# IO_board2.net
KiCad netlist of a schematic drawn in Altium Designer
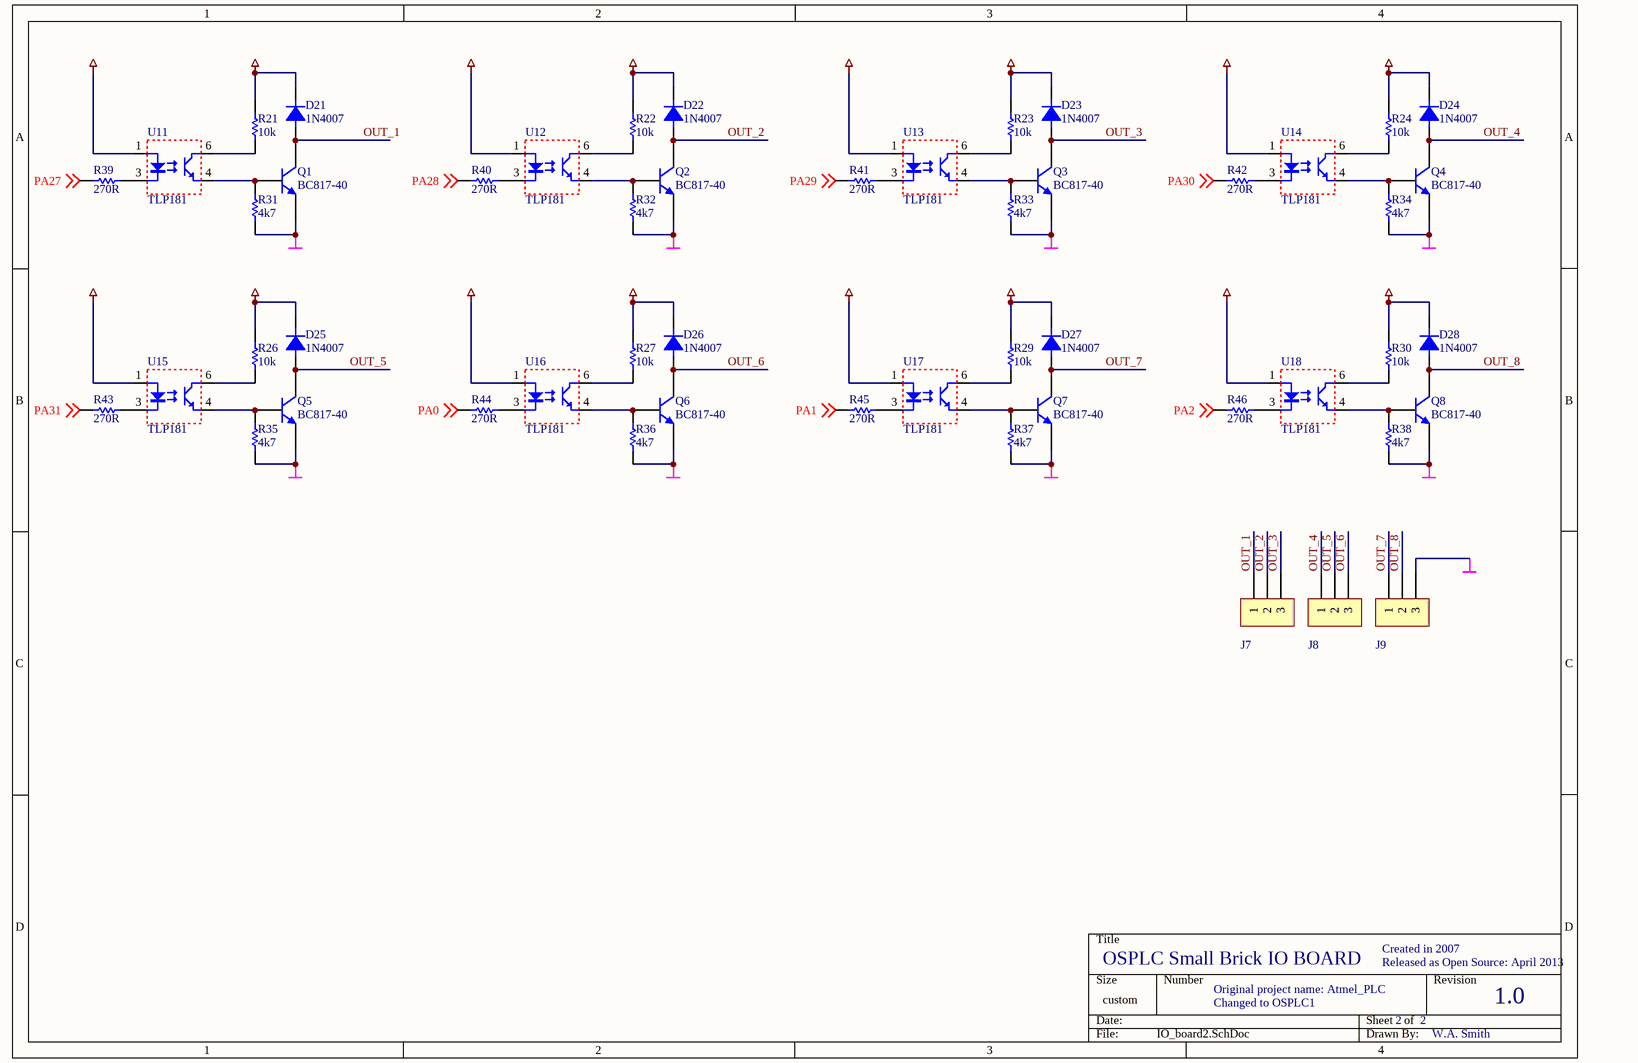
[diagram p0: IO_board2.SchDoc]

(export (version "E")
  (design (tool "Eeschema 10.0.6"))
  (components
    (comp (ref "D21")
      (value "1N4007 Radialy Mounted")
      (footprint "DIODE_RAD_3MM")
      (description "1N4007 Rectifier Diode Radialy Mounted")
      (fields (field (name "ALTIUM_VALUE") "1N4007"))
      (libsource (lib "ARM_projects") (part "1N4007"))
    )
    (comp (ref "D22")
      (value "1N4007 Radialy Mounted")
      (footprint "DIODE_RAD_3MM")
      (description "1N4007 Rectifier Diode Radialy Mounted")
      (fields (field (name "ALTIUM_VALUE") "1N4007"))
      (libsource (lib "ARM_projects") (part "1N4007"))
    )
    (comp (ref "D23")
      (value "1N4007 Radialy Mounted")
      (footprint "DIODE_RAD_3MM")
      (description "1N4007 Rectifier Diode Radialy Mounted")
      (fields (field (name "ALTIUM_VALUE") "1N4007"))
      (libsource (lib "ARM_projects") (part "1N4007"))
    )
    (comp (ref "D24")
      (value "1N4007 Radialy Mounted")
      (footprint "DIODE_RAD_3MM")
      (description "1N4007 Rectifier Diode Radialy Mounted")
      (fields (field (name "ALTIUM_VALUE") "1N4007"))
      (libsource (lib "ARM_projects") (part "1N4007"))
    )
    (comp (ref "D25")
      (value "1N4007 Radialy Mounted")
      (footprint "DIODE_RAD_3MM")
      (description "1N4007 Rectifier Diode Radialy Mounted")
      (fields (field (name "ALTIUM_VALUE") "1N4007"))
      (libsource (lib "ARM_projects") (part "1N4007"))
    )
    (comp (ref "D26")
      (value "1N4007 Radialy Mounted")
      (footprint "DIODE_RAD_3MM")
      (description "1N4007 Rectifier Diode Radialy Mounted")
      (fields (field (name "ALTIUM_VALUE") "1N4007"))
      (libsource (lib "ARM_projects") (part "1N4007"))
    )
    (comp (ref "D27")
      (value "1N4007 Radialy Mounted")
      (footprint "DIODE_RAD_3MM")
      (description "1N4007 Rectifier Diode Radialy Mounted")
      (fields (field (name "ALTIUM_VALUE") "1N4007"))
      (libsource (lib "ARM_projects") (part "1N4007"))
    )
    (comp (ref "D28")
      (value "1N4007 Radialy Mounted")
      (footprint "DIODE_RAD_3MM")
      (description "1N4007 Rectifier Diode Radialy Mounted")
      (fields (field (name "ALTIUM_VALUE") "1N4007"))
      (libsource (lib "ARM_projects") (part "1N4007"))
    )
    (comp (ref "J7")
      (value "PCB TERMINAL")
      (footprint "TERMINAL_3WAY_5MM")
      (description "5mm spaced PCB terminal, 3 pole")
      (libsource (lib "ARM_projects") (part "TERMINAL_3WAY_5MM"))
    )
    (comp (ref "J8")
      (value "PCB TERMINAL")
      (footprint "TERMINAL_3WAY_5MM")
      (description "5mm spaced PCB terminal, 3 pole")
      (libsource (lib "ARM_projects") (part "TERMINAL_3WAY_5MM"))
    )
    (comp (ref "J9")
      (value "PCB TERMINAL")
      (footprint "TERMINAL_3WAY_5MM")
      (description "5mm spaced PCB terminal, 3 pole")
      (libsource (lib "ARM_projects") (part "TERMINAL_3WAY_5MM"))
    )
    (comp (ref "Q1")
      (value "BC817-40")
      (footprint "SO-G3/Y1")
      (description "NPN General Purpose Amplifier")
      (fields
        (field (name "MANUFACTURER") "Fairchild Semiconductor")
        (field (name "PUBLISHER") "Altium Limited")
      )
      (libsource (lib "FSC Discrete BJT") (part "BC817-40"))
    )
    (comp (ref "Q2")
      (value "BC817-40")
      (footprint "SO-G3/Y1")
      (description "NPN General Purpose Amplifier")
      (fields
        (field (name "MANUFACTURER") "Fairchild Semiconductor")
        (field (name "PUBLISHER") "Altium Limited")
      )
      (libsource (lib "FSC Discrete BJT") (part "BC817-40"))
    )
    (comp (ref "Q3")
      (value "BC817-40")
      (footprint "SO-G3/Y1")
      (description "NPN General Purpose Amplifier")
      (fields
        (field (name "MANUFACTURER") "Fairchild Semiconductor")
        (field (name "PUBLISHER") "Altium Limited")
      )
      (libsource (lib "FSC Discrete BJT") (part "BC817-40"))
    )
    (comp (ref "Q4")
      (value "BC817-40")
      (footprint "SO-G3/Y1")
      (description "NPN General Purpose Amplifier")
      (fields
        (field (name "MANUFACTURER") "Fairchild Semiconductor")
        (field (name "PUBLISHER") "Altium Limited")
      )
      (libsource (lib "FSC Discrete BJT") (part "BC817-40"))
    )
    (comp (ref "Q5")
      (value "BC817-40")
      (footprint "SO-G3/Y1")
      (description "NPN General Purpose Amplifier")
      (fields
        (field (name "MANUFACTURER") "Fairchild Semiconductor")
        (field (name "PUBLISHER") "Altium Limited")
      )
      (libsource (lib "FSC Discrete BJT") (part "BC817-40"))
    )
    (comp (ref "Q6")
      (value "BC817-40")
      (footprint "SO-G3/Y1")
      (description "NPN General Purpose Amplifier")
      (fields
        (field (name "MANUFACTURER") "Fairchild Semiconductor")
        (field (name "PUBLISHER") "Altium Limited")
      )
      (libsource (lib "FSC Discrete BJT") (part "BC817-40"))
    )
    (comp (ref "Q7")
      (value "BC817-40")
      (footprint "SO-G3/Y1")
      (description "NPN General Purpose Amplifier")
      (fields
        (field (name "MANUFACTURER") "Fairchild Semiconductor")
        (field (name "PUBLISHER") "Altium Limited")
      )
      (libsource (lib "FSC Discrete BJT") (part "BC817-40"))
    )
    (comp (ref "Q8")
      (value "BC817-40")
      (footprint "SO-G3/Y1")
      (description "NPN General Purpose Amplifier")
      (fields
        (field (name "MANUFACTURER") "Fairchild Semiconductor")
        (field (name "PUBLISHER") "Altium Limited")
      )
      (libsource (lib "FSC Discrete BJT") (part "BC817-40"))
    )
    (comp (ref "R21")
      (value "0805")
      (footprint "0805")
      (description "0805 footprint resistor")
      (fields (field (name "ALTIUM_VALUE") "10k"))
      (libsource (lib "Integrated Comp_lib") (part "RES_0805"))
    )
    (comp (ref "R22")
      (value "0805")
      (footprint "0805")
      (description "0805 footprint resistor")
      (fields (field (name "ALTIUM_VALUE") "10k"))
      (libsource (lib "Integrated Comp_lib") (part "RES_0805"))
    )
    (comp (ref "R23")
      (value "0805")
      (footprint "0805")
      (description "0805 footprint resistor")
      (fields (field (name "ALTIUM_VALUE") "10k"))
      (libsource (lib "Integrated Comp_lib") (part "RES_0805"))
    )
    (comp (ref "R24")
      (value "0805")
      (footprint "0805")
      (description "0805 footprint resistor")
      (fields (field (name "ALTIUM_VALUE") "10k"))
      (libsource (lib "Integrated Comp_lib") (part "RES_0805"))
    )
    (comp (ref "R26")
      (value "0805")
      (footprint "0805")
      (description "0805 footprint resistor")
      (fields (field (name "ALTIUM_VALUE") "10k"))
      (libsource (lib "Integrated Comp_lib") (part "RES_0805"))
    )
    (comp (ref "R27")
      (value "0805")
      (footprint "0805")
      (description "0805 footprint resistor")
      (fields (field (name "ALTIUM_VALUE") "10k"))
      (libsource (lib "Integrated Comp_lib") (part "RES_0805"))
    )
    (comp (ref "R29")
      (value "0805")
      (footprint "0805")
      (description "0805 footprint resistor")
      (fields (field (name "ALTIUM_VALUE") "10k"))
      (libsource (lib "Integrated Comp_lib") (part "RES_0805"))
    )
    (comp (ref "R30")
      (value "0805")
      (footprint "0805")
      (description "0805 footprint resistor")
      (fields (field (name "ALTIUM_VALUE") "10k"))
      (libsource (lib "Integrated Comp_lib") (part "RES_0805"))
    )
    (comp (ref "R31")
      (value "0805")
      (footprint "0805")
      (description "0805 footprint resistor")
      (fields (field (name "ALTIUM_VALUE") "4k7"))
      (libsource (lib "Integrated Comp_lib") (part "RES_0805"))
    )
    (comp (ref "R32")
      (value "0805")
      (footprint "0805")
      (description "0805 footprint resistor")
      (fields (field (name "ALTIUM_VALUE") "4k7"))
      (libsource (lib "Integrated Comp_lib") (part "RES_0805"))
    )
    (comp (ref "R33")
      (value "0805")
      (footprint "0805")
      (description "0805 footprint resistor")
      (fields (field (name "ALTIUM_VALUE") "4k7"))
      (libsource (lib "Integrated Comp_lib") (part "RES_0805"))
    )
    (comp (ref "R34")
      (value "0805")
      (footprint "0805")
      (description "0805 footprint resistor")
      (fields (field (name "ALTIUM_VALUE") "4k7"))
      (libsource (lib "Integrated Comp_lib") (part "RES_0805"))
    )
    (comp (ref "R35")
      (value "0805")
      (footprint "0805")
      (description "0805 footprint resistor")
      (fields (field (name "ALTIUM_VALUE") "4k7"))
      (libsource (lib "Integrated Comp_lib") (part "RES_0805"))
    )
    (comp (ref "R36")
      (value "0805")
      (footprint "0805")
      (description "0805 footprint resistor")
      (fields (field (name "ALTIUM_VALUE") "4k7"))
      (libsource (lib "Integrated Comp_lib") (part "RES_0805"))
    )
    (comp (ref "R37")
      (value "0805")
      (footprint "0805")
      (description "0805 footprint resistor")
      (fields (field (name "ALTIUM_VALUE") "4k7"))
      (libsource (lib "Integrated Comp_lib") (part "RES_0805"))
    )
    (comp (ref "R38")
      (value "0805")
      (footprint "0805")
      (description "0805 footprint resistor")
      (fields (field (name "ALTIUM_VALUE") "4k7"))
      (libsource (lib "Integrated Comp_lib") (part "RES_0805"))
    )
    (comp (ref "R39")
      (value "0805")
      (footprint "0805")
      (description "0805 footprint resistor")
      (fields (field (name "ALTIUM_VALUE") "270R"))
      (libsource (lib "Integrated Comp_lib") (part "RES_0805"))
    )
    (comp (ref "R40")
      (value "0805")
      (footprint "0805")
      (description "0805 footprint resistor")
      (fields (field (name "ALTIUM_VALUE") "270R"))
      (libsource (lib "Integrated Comp_lib") (part "RES_0805"))
    )
    (comp (ref "R41")
      (value "0805")
      (footprint "0805")
      (description "0805 footprint resistor")
      (fields (field (name "ALTIUM_VALUE") "270R"))
      (libsource (lib "Integrated Comp_lib") (part "RES_0805"))
    )
    (comp (ref "R42")
      (value "0805")
      (footprint "0805")
      (description "0805 footprint resistor")
      (fields (field (name "ALTIUM_VALUE") "270R"))
      (libsource (lib "Integrated Comp_lib") (part "RES_0805"))
    )
    (comp (ref "R43")
      (value "0805")
      (footprint "0805")
      (description "0805 footprint resistor")
      (fields (field (name "ALTIUM_VALUE") "270R"))
      (libsource (lib "Integrated Comp_lib") (part "RES_0805"))
    )
    (comp (ref "R44")
      (value "0805")
      (footprint "0805")
      (description "0805 footprint resistor")
      (fields (field (name "ALTIUM_VALUE") "270R"))
      (libsource (lib "Integrated Comp_lib") (part "RES_0805"))
    )
    (comp (ref "R45")
      (value "0805")
      (footprint "0805")
      (description "0805 footprint resistor")
      (fields (field (name "ALTIUM_VALUE") "270R"))
      (libsource (lib "Integrated Comp_lib") (part "RES_0805"))
    )
    (comp (ref "R46")
      (value "0805")
      (footprint "0805")
      (description "0805 footprint resistor")
      (fields (field (name "ALTIUM_VALUE") "270R"))
      (libsource (lib "Integrated Comp_lib") (part "RES_0805"))
    )
    (comp (ref "U11")
      (value "TLP181")
      (footprint "SOP4_2.54")
      (description "Toshiba Photocoupler")
      (libsource (lib "Integrated Comp_lib") (part "TLP181"))
    )
    (comp (ref "U12")
      (value "TLP181")
      (footprint "SOP4_2.54")
      (description "Toshiba Photocoupler")
      (libsource (lib "Integrated Comp_lib") (part "TLP181"))
    )
    (comp (ref "U13")
      (value "TLP181")
      (footprint "SOP4_2.54")
      (description "Toshiba Photocoupler")
      (libsource (lib "Integrated Comp_lib") (part "TLP181"))
    )
    (comp (ref "U14")
      (value "TLP181")
      (footprint "SOP4_2.54")
      (description "Toshiba Photocoupler")
      (libsource (lib "Integrated Comp_lib") (part "TLP181"))
    )
    (comp (ref "U15")
      (value "TLP181")
      (footprint "SOP4_2.54")
      (description "Toshiba Photocoupler")
      (libsource (lib "Integrated Comp_lib") (part "TLP181"))
    )
    (comp (ref "U16")
      (value "TLP181")
      (footprint "SOP4_2.54")
      (description "Toshiba Photocoupler")
      (libsource (lib "Integrated Comp_lib") (part "TLP181"))
    )
    (comp (ref "U17")
      (value "TLP181")
      (footprint "SOP4_2.54")
      (description "Toshiba Photocoupler")
      (libsource (lib "Integrated Comp_lib") (part "TLP181"))
    )
    (comp (ref "U18")
      (value "TLP181")
      (footprint "SOP4_2.54")
      (description "Toshiba Photocoupler")
      (libsource (lib "Integrated Comp_lib") (part "TLP181"))
    )
  )
  (nets
    (net (code "1") (name "/OUT_1") (class "Default")
      (node (ref "D21") (pin "2") (pinfunction "A_2") (pintype "passive"))
      (node (ref "J7") (pin "1") (pinfunction "1_1") (pintype "passive"))
      (node (ref "Q1") (pin "3") (pinfunction "C_3") (pintype "passive"))
    )
    (net (code "2") (name "/OUT_2") (class "Default")
      (node (ref "D22") (pin "2") (pinfunction "A_2") (pintype "passive"))
      (node (ref "J7") (pin "2") (pinfunction "2_2") (pintype "passive"))
      (node (ref "Q2") (pin "3") (pinfunction "C_3") (pintype "passive"))
    )
    (net (code "3") (name "/OUT_3") (class "Default")
      (node (ref "D23") (pin "2") (pinfunction "A_2") (pintype "passive"))
      (node (ref "J7") (pin "3") (pinfunction "3_3") (pintype "passive"))
      (node (ref "Q3") (pin "3") (pinfunction "C_3") (pintype "passive"))
    )
    (net (code "4") (name "/OUT_4") (class "Default")
      (node (ref "D24") (pin "2") (pinfunction "A_2") (pintype "passive"))
      (node (ref "J8") (pin "1") (pinfunction "1_1") (pintype "passive"))
      (node (ref "Q4") (pin "3") (pinfunction "C_3") (pintype "passive"))
    )
    (net (code "5") (name "/OUT_5") (class "Default")
      (node (ref "D25") (pin "2") (pinfunction "A_2") (pintype "passive"))
      (node (ref "J8") (pin "2") (pinfunction "2_2") (pintype "passive"))
      (node (ref "Q5") (pin "3") (pinfunction "C_3") (pintype "passive"))
    )
    (net (code "6") (name "/OUT_6") (class "Default")
      (node (ref "D26") (pin "2") (pinfunction "A_2") (pintype "passive"))
      (node (ref "J8") (pin "3") (pinfunction "3_3") (pintype "passive"))
      (node (ref "Q6") (pin "3") (pinfunction "C_3") (pintype "passive"))
    )
    (net (code "7") (name "/OUT_7") (class "Default")
      (node (ref "D27") (pin "2") (pinfunction "A_2") (pintype "passive"))
      (node (ref "J9") (pin "1") (pinfunction "1_1") (pintype "passive"))
      (node (ref "Q7") (pin "3") (pinfunction "C_3") (pintype "passive"))
    )
    (net (code "8") (name "/OUT_8") (class "Default")
      (node (ref "D28") (pin "2") (pinfunction "A_2") (pintype "passive"))
      (node (ref "J9") (pin "2") (pinfunction "2_2") (pintype "passive"))
      (node (ref "Q8") (pin "3") (pinfunction "C_3") (pintype "passive"))
    )
    (net (code "9") (name "Net-(Q1-B)") (class "Default")
      (node (ref "Q1") (pin "1") (pinfunction "B_1") (pintype "passive"))
      (node (ref "R31") (pin "2") (pinfunction "2_2") (pintype "passive"))
      (node (ref "U11") (pin "4") (pinfunction "4_4") (pintype "passive"))
    )
    (net (code "10") (name "Net-(Q2-B)") (class "Default")
      (node (ref "Q2") (pin "1") (pinfunction "B_1") (pintype "passive"))
      (node (ref "R32") (pin "2") (pinfunction "2_2") (pintype "passive"))
      (node (ref "U12") (pin "4") (pinfunction "4_4") (pintype "passive"))
    )
    (net (code "11") (name "Net-(Q3-B)") (class "Default")
      (node (ref "Q3") (pin "1") (pinfunction "B_1") (pintype "passive"))
      (node (ref "R33") (pin "2") (pinfunction "2_2") (pintype "passive"))
      (node (ref "U13") (pin "4") (pinfunction "4_4") (pintype "passive"))
    )
    (net (code "12") (name "Net-(Q4-B)") (class "Default")
      (node (ref "Q4") (pin "1") (pinfunction "B_1") (pintype "passive"))
      (node (ref "R34") (pin "2") (pinfunction "2_2") (pintype "passive"))
      (node (ref "U14") (pin "4") (pinfunction "4_4") (pintype "passive"))
    )
    (net (code "13") (name "Net-(Q5-B)") (class "Default")
      (node (ref "Q5") (pin "1") (pinfunction "B_1") (pintype "passive"))
      (node (ref "R35") (pin "2") (pinfunction "2_2") (pintype "passive"))
      (node (ref "U15") (pin "4") (pinfunction "4_4") (pintype "passive"))
    )
    (net (code "14") (name "Net-(Q6-B)") (class "Default")
      (node (ref "Q6") (pin "1") (pinfunction "B_1") (pintype "passive"))
      (node (ref "R36") (pin "2") (pinfunction "2_2") (pintype "passive"))
      (node (ref "U16") (pin "4") (pinfunction "4_4") (pintype "passive"))
    )
    (net (code "15") (name "Net-(Q7-B)") (class "Default")
      (node (ref "Q7") (pin "1") (pinfunction "B_1") (pintype "passive"))
      (node (ref "R37") (pin "2") (pinfunction "2_2") (pintype "passive"))
      (node (ref "U17") (pin "4") (pinfunction "4_4") (pintype "passive"))
    )
    (net (code "16") (name "Net-(Q8-B)") (class "Default")
      (node (ref "Q8") (pin "1") (pinfunction "B_1") (pintype "passive"))
      (node (ref "R38") (pin "2") (pinfunction "2_2") (pintype "passive"))
      (node (ref "U18") (pin "4") (pinfunction "4_4") (pintype "passive"))
    )
    (net (code "17") (name "Net-(R21-Pad1)") (class "Default")
      (node (ref "R21") (pin "1") (pinfunction "1_1") (pintype "passive"))
      (node (ref "U11") (pin "6") (pinfunction "6_6") (pintype "passive"))
    )
    (net (code "18") (name "Net-(R22-Pad1)") (class "Default")
      (node (ref "R22") (pin "1") (pinfunction "1_1") (pintype "passive"))
      (node (ref "U12") (pin "6") (pinfunction "6_6") (pintype "passive"))
    )
    (net (code "19") (name "Net-(R23-Pad1)") (class "Default")
      (node (ref "R23") (pin "1") (pinfunction "1_1") (pintype "passive"))
      (node (ref "U13") (pin "6") (pinfunction "6_6") (pintype "passive"))
    )
    (net (code "20") (name "Net-(R24-Pad1)") (class "Default")
      (node (ref "R24") (pin "1") (pinfunction "1_1") (pintype "passive"))
      (node (ref "U14") (pin "6") (pinfunction "6_6") (pintype "passive"))
    )
    (net (code "21") (name "Net-(R26-Pad1)") (class "Default")
      (node (ref "R26") (pin "1") (pinfunction "1_1") (pintype "passive"))
      (node (ref "U15") (pin "6") (pinfunction "6_6") (pintype "passive"))
    )
    (net (code "22") (name "Net-(R27-Pad1)") (class "Default")
      (node (ref "R27") (pin "1") (pinfunction "1_1") (pintype "passive"))
      (node (ref "U16") (pin "6") (pinfunction "6_6") (pintype "passive"))
    )
    (net (code "23") (name "Net-(R29-Pad1)") (class "Default")
      (node (ref "R29") (pin "1") (pinfunction "1_1") (pintype "passive"))
      (node (ref "U17") (pin "6") (pinfunction "6_6") (pintype "passive"))
    )
    (net (code "24") (name "Net-(R30-Pad1)") (class "Default")
      (node (ref "R30") (pin "1") (pinfunction "1_1") (pintype "passive"))
      (node (ref "U18") (pin "6") (pinfunction "6_6") (pintype "passive"))
    )
    (net (code "25") (name "Net-(R39-Pad2)") (class "Default")
      (node (ref "R39") (pin "2") (pinfunction "2_2") (pintype "passive"))
      (node (ref "U11") (pin "3") (pinfunction "3_3") (pintype "passive"))
    )
    (net (code "26") (name "Net-(R40-Pad2)") (class "Default")
      (node (ref "R40") (pin "2") (pinfunction "2_2") (pintype "passive"))
      (node (ref "U12") (pin "3") (pinfunction "3_3") (pintype "passive"))
    )
    (net (code "27") (name "Net-(R41-Pad2)") (class "Default")
      (node (ref "R41") (pin "2") (pinfunction "2_2") (pintype "passive"))
      (node (ref "U13") (pin "3") (pinfunction "3_3") (pintype "passive"))
    )
    (net (code "28") (name "Net-(R42-Pad2)") (class "Default")
      (node (ref "R42") (pin "2") (pinfunction "2_2") (pintype "passive"))
      (node (ref "U14") (pin "3") (pinfunction "3_3") (pintype "passive"))
    )
    (net (code "29") (name "Net-(R43-Pad2)") (class "Default")
      (node (ref "R43") (pin "2") (pinfunction "2_2") (pintype "passive"))
      (node (ref "U15") (pin "3") (pinfunction "3_3") (pintype "passive"))
    )
    (net (code "30") (name "Net-(R44-Pad2)") (class "Default")
      (node (ref "R44") (pin "2") (pinfunction "2_2") (pintype "passive"))
      (node (ref "U16") (pin "3") (pinfunction "3_3") (pintype "passive"))
    )
    (net (code "31") (name "Net-(R45-Pad2)") (class "Default")
      (node (ref "R45") (pin "2") (pinfunction "2_2") (pintype "passive"))
      (node (ref "U17") (pin "3") (pinfunction "3_3") (pintype "passive"))
    )
    (net (code "32") (name "Net-(R46-Pad2)") (class "Default")
      (node (ref "R46") (pin "2") (pinfunction "2_2") (pintype "passive"))
      (node (ref "U18") (pin "3") (pinfunction "3_3") (pintype "passive"))
    )
    (net (code "33") (name "OUT_GND") (class "Default")
      (node (ref "J9") (pin "3") (pinfunction "3_3") (pintype "passive"))
      (node (ref "Q1") (pin "2") (pinfunction "E_2") (pintype "passive"))
      (node (ref "Q2") (pin "2") (pinfunction "E_2") (pintype "passive"))
      (node (ref "Q3") (pin "2") (pinfunction "E_2") (pintype "passive"))
      (node (ref "Q4") (pin "2") (pinfunction "E_2") (pintype "passive"))
      (node (ref "Q5") (pin "2") (pinfunction "E_2") (pintype "passive"))
      (node (ref "Q6") (pin "2") (pinfunction "E_2") (pintype "passive"))
      (node (ref "Q7") (pin "2") (pinfunction "E_2") (pintype "passive"))
      (node (ref "Q8") (pin "2") (pinfunction "E_2") (pintype "passive"))
      (node (ref "R31") (pin "1") (pinfunction "1_1") (pintype "passive"))
      (node (ref "R32") (pin "1") (pinfunction "1_1") (pintype "passive"))
      (node (ref "R33") (pin "1") (pinfunction "1_1") (pintype "passive"))
      (node (ref "R34") (pin "1") (pinfunction "1_1") (pintype "passive"))
      (node (ref "R35") (pin "1") (pinfunction "1_1") (pintype "passive"))
      (node (ref "R36") (pin "1") (pinfunction "1_1") (pintype "passive"))
      (node (ref "R37") (pin "1") (pinfunction "1_1") (pintype "passive"))
      (node (ref "R38") (pin "1") (pinfunction "1_1") (pintype "passive"))
    )
    (net (code "34") (name "PA0") (class "Default")
      (node (ref "R44") (pin "1") (pinfunction "1_1") (pintype "passive"))
    )
    (net (code "35") (name "PA1") (class "Default")
      (node (ref "R45") (pin "1") (pinfunction "1_1") (pintype "passive"))
    )
    (net (code "36") (name "PA2") (class "Default")
      (node (ref "R46") (pin "1") (pinfunction "1_1") (pintype "passive"))
    )
    (net (code "37") (name "PA27") (class "Default")
      (node (ref "R39") (pin "1") (pinfunction "1_1") (pintype "passive"))
    )
    (net (code "38") (name "PA28") (class "Default")
      (node (ref "R40") (pin "1") (pinfunction "1_1") (pintype "passive"))
    )
    (net (code "39") (name "PA29") (class "Default")
      (node (ref "R41") (pin "1") (pinfunction "1_1") (pintype "passive"))
    )
    (net (code "40") (name "PA30") (class "Default")
      (node (ref "R42") (pin "1") (pinfunction "1_1") (pintype "passive"))
    )
    (net (code "41") (name "PA31") (class "Default")
      (node (ref "R43") (pin "1") (pinfunction "1_1") (pintype "passive"))
    )
    (net (code "42") (name "VCC3v3") (class "Default")
      (node (ref "U11") (pin "1") (pinfunction "1_1") (pintype "passive"))
      (node (ref "U12") (pin "1") (pinfunction "1_1") (pintype "passive"))
      (node (ref "U13") (pin "1") (pinfunction "1_1") (pintype "passive"))
      (node (ref "U14") (pin "1") (pinfunction "1_1") (pintype "passive"))
      (node (ref "U15") (pin "1") (pinfunction "1_1") (pintype "passive"))
      (node (ref "U16") (pin "1") (pinfunction "1_1") (pintype "passive"))
      (node (ref "U17") (pin "1") (pinfunction "1_1") (pintype "passive"))
      (node (ref "U18") (pin "1") (pinfunction "1_1") (pintype "passive"))
    )
    (net (code "43") (name "VCC24") (class "Default")
      (node (ref "D21") (pin "1") (pinfunction "C_1") (pintype "passive"))
      (node (ref "D22") (pin "1") (pinfunction "C_1") (pintype "passive"))
      (node (ref "D23") (pin "1") (pinfunction "C_1") (pintype "passive"))
      (node (ref "D24") (pin "1") (pinfunction "C_1") (pintype "passive"))
      (node (ref "D25") (pin "1") (pinfunction "C_1") (pintype "passive"))
      (node (ref "D26") (pin "1") (pinfunction "C_1") (pintype "passive"))
      (node (ref "D27") (pin "1") (pinfunction "C_1") (pintype "passive"))
      (node (ref "D28") (pin "1") (pinfunction "C_1") (pintype "passive"))
      (node (ref "R21") (pin "2") (pinfunction "2_2") (pintype "passive"))
      (node (ref "R22") (pin "2") (pinfunction "2_2") (pintype "passive"))
      (node (ref "R23") (pin "2") (pinfunction "2_2") (pintype "passive"))
      (node (ref "R24") (pin "2") (pinfunction "2_2") (pintype "passive"))
      (node (ref "R26") (pin "2") (pinfunction "2_2") (pintype "passive"))
      (node (ref "R27") (pin "2") (pinfunction "2_2") (pintype "passive"))
      (node (ref "R29") (pin "2") (pinfunction "2_2") (pintype "passive"))
      (node (ref "R30") (pin "2") (pinfunction "2_2") (pintype "passive"))
    )
  )
)
